# VA-Meter.net
KiCad netlist of a schematic drawn in EAGLE
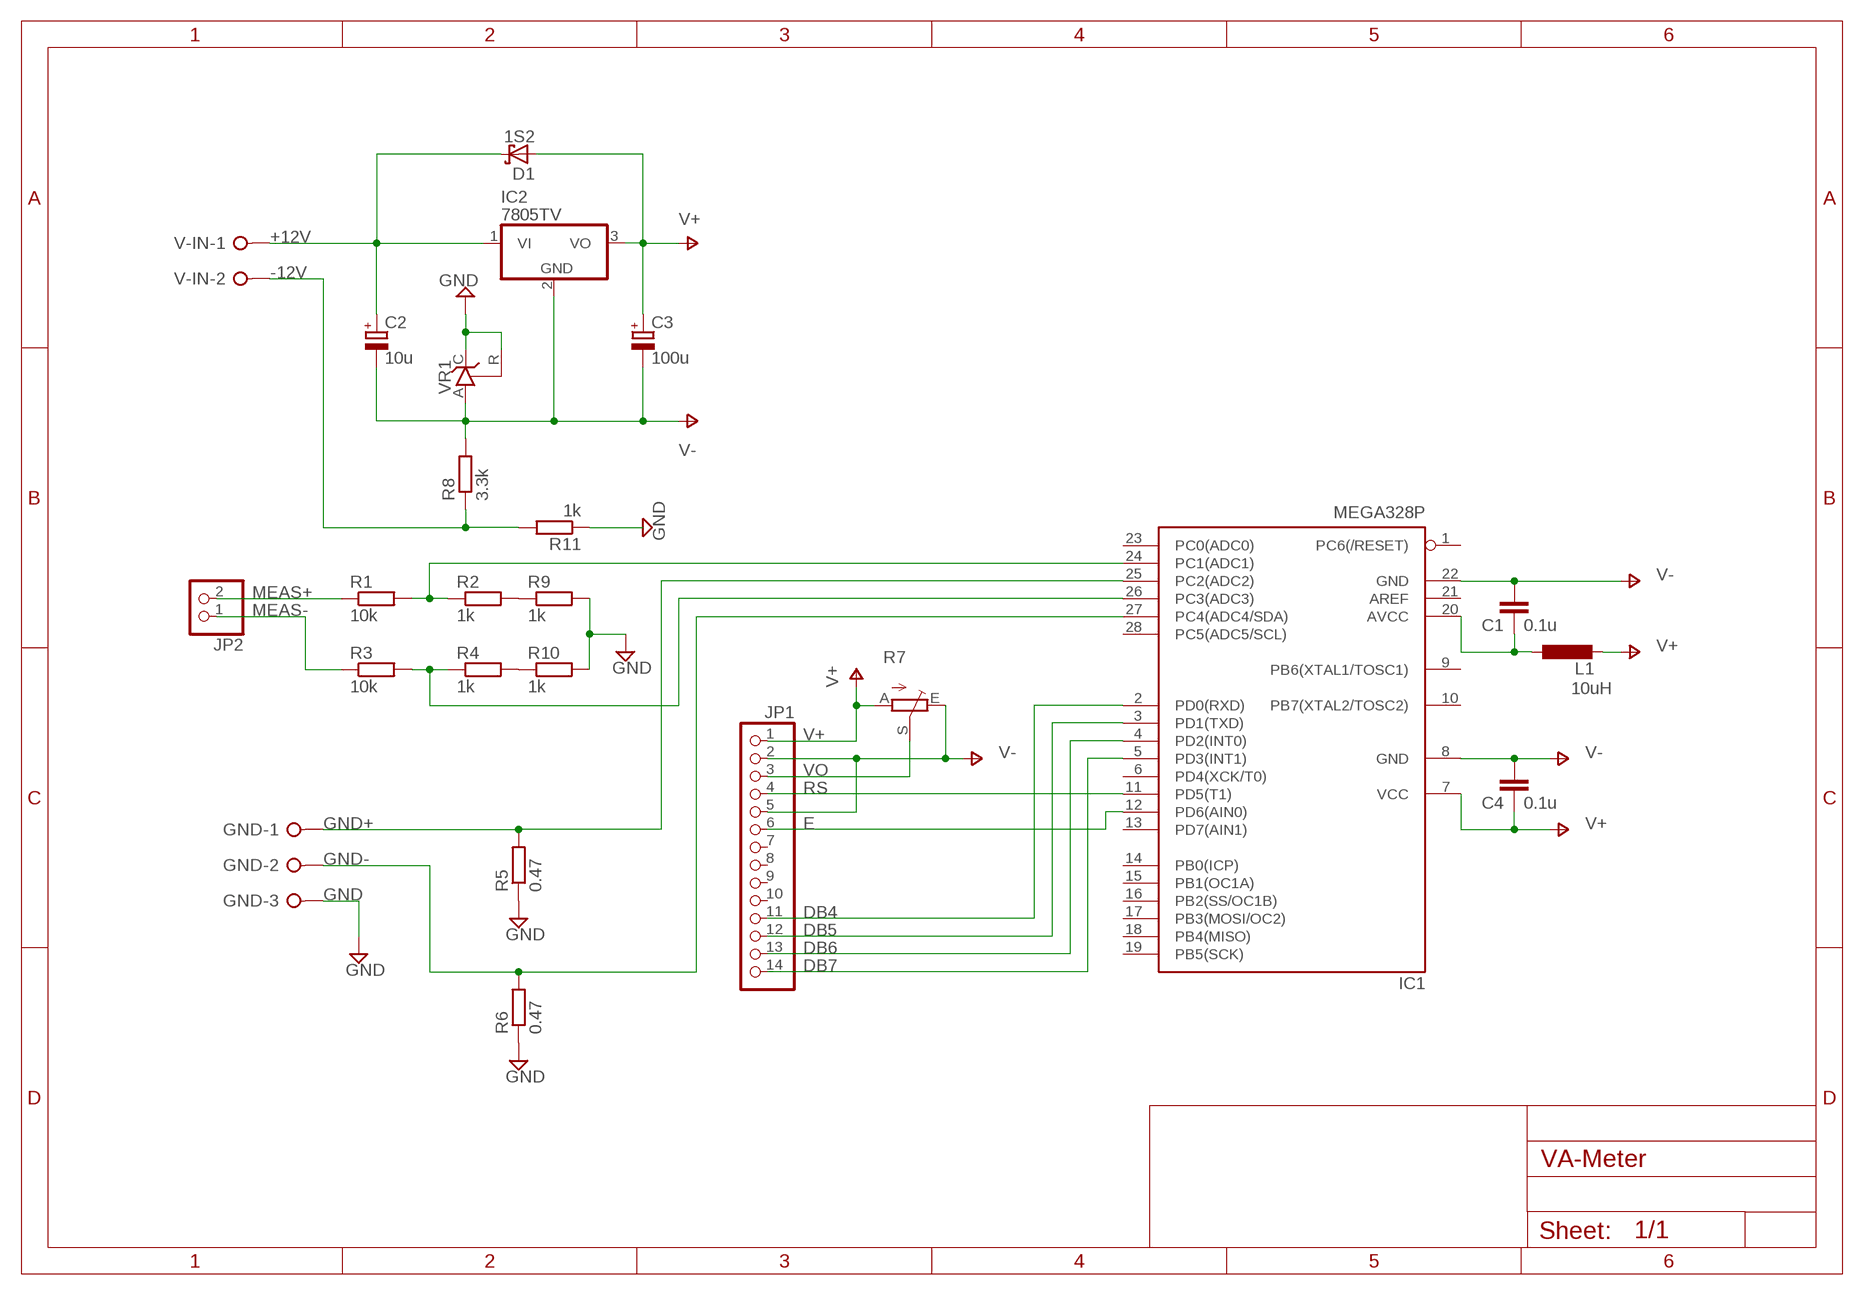
[diagram p0: schematic, sheet 1]

(export (version "E")
  (design (tool "Eeschema 10.0.6"))
  (components
    (comp (ref "C1")
      (value "0.1u")
      (footprint "eagle-import:C050-024X044")
      (libsource (lib "eagle-import") (part "C-EU050-024X044"))
    )
    (comp (ref "C2")
      (value "10u")
      (footprint "eagle-import:E2,5-5")
      (libsource (lib "eagle-import") (part "CPOL-EUE2.5-5"))
    )
    (comp (ref "C3")
      (value "100u")
      (footprint "eagle-import:E2,5-6")
      (libsource (lib "eagle-import") (part "CPOL-EUE2.5-6"))
    )
    (comp (ref "C4")
      (value "0.1u")
      (footprint "eagle-import:C050-024X044")
      (libsource (lib "eagle-import") (part "C-EU050-024X044"))
    )
    (comp (ref "D1")
      (value "1S2")
      (footprint "eagle-import:CB417-15")
      (libsource (lib "eagle-import") (part "SCHOTTKY-DIODECB417-15"))
    )
    (comp (ref "GND")
      (value "W237-03P")
      (footprint "eagle-import:W237-133")
      (libsource (lib "eagle-import") (part "W237-03P"))
    )
    (comp (ref "IC1")
      (value "MEGA328P")
      (footprint "eagle-import:MEGA328P")
      (libsource (lib "eagle-import") (part "MEGA328P"))
    )
    (comp (ref "IC2")
      (value "7805TV")
      (footprint "eagle-import:TO220V")
      (libsource (lib "eagle-import") (part "78TV05"))
    )
    (comp (ref "JP1")
      (value "PINHD-1X14")
      (footprint "eagle-import:1X14")
      (libsource (lib "eagle-import") (part "PINHD-1X14"))
    )
    (comp (ref "JP2")
      (value "PINHD-1X2")
      (footprint "eagle-import:1X02")
      (libsource (lib "eagle-import") (part "PINHD-1X2"))
    )
    (comp (ref "L1")
      (value "10uH")
      (footprint "eagle-import:6000-XXXX-RC")
      (libsource (lib "eagle-import") (part "L-EU6000-XXX-RC"))
    )
    (comp (ref "R1")
      (value "10k")
      (footprint "eagle-import:0207_7")
      (libsource (lib "eagle-import") (part "R-EU_0207/7"))
    )
    (comp (ref "R2")
      (value "1k")
      (footprint "eagle-import:0207_7")
      (libsource (lib "eagle-import") (part "R-EU_0207/7"))
    )
    (comp (ref "R3")
      (value "10k")
      (footprint "eagle-import:0207_7")
      (libsource (lib "eagle-import") (part "R-EU_0207/7"))
    )
    (comp (ref "R4")
      (value "1k")
      (footprint "eagle-import:0207_7")
      (libsource (lib "eagle-import") (part "R-EU_0207/7"))
    )
    (comp (ref "R5")
      (value "0.47")
      (footprint "eagle-import:P0613_15")
      (libsource (lib "eagle-import") (part "R-EU_0613/15"))
    )
    (comp (ref "R6")
      (value "0.47")
      (footprint "eagle-import:P0613_15")
      (libsource (lib "eagle-import") (part "R-EU_0613/15"))
    )
    (comp (ref "R7")
      (value "TRIM_EU-B25P")
      (footprint "eagle-import:B25P")
      (libsource (lib "eagle-import") (part "TRIM_EU-B25P"))
    )
    (comp (ref "R8")
      (value "3.3k")
      (footprint "eagle-import:P0613_15")
      (libsource (lib "eagle-import") (part "R-EU_0613/15"))
    )
    (comp (ref "R9")
      (value "1k")
      (footprint "eagle-import:0207_7")
      (libsource (lib "eagle-import") (part "R-EU_0207/7"))
    )
    (comp (ref "R10")
      (value "1k")
      (footprint "eagle-import:0207_7")
      (libsource (lib "eagle-import") (part "R-EU_0207/7"))
    )
    (comp (ref "R11")
      (value "1k")
      (footprint "eagle-import:P0613_15")
      (libsource (lib "eagle-import") (part "R-EU_0613/15"))
    )
    (comp (ref "V-IN")
      (value "W237-02P")
      (footprint "eagle-import:W237-132")
      (libsource (lib "eagle-import") (part "W237-02P"))
    )
    (comp (ref "VR1")
      (value "TL431CLP")
      (footprint "eagle-import:TO92-CLP")
      (libsource (lib "eagle-import") (part "TL431CLP"))
    )
  )
  (nets
    (net (code "1") (name "/+12V") (class "Default")
      (node (ref "C2") (pin "+") (pinfunction "+_+") (pintype "passive"))
      (node (ref "D1") (pin "C") (pinfunction "C_C") (pintype "passive"))
      (node (ref "IC2") (pin "1") (pinfunction "VI_1") (pintype "input"))
      (node (ref "V-IN") (pin "1") (pinfunction "KL_1") (pintype "passive"))
    )
    (net (code "2") (name "/-12V") (class "Default")
      (node (ref "R11") (pin "2") (pinfunction "2_2") (pintype "passive"))
      (node (ref "R8") (pin "1") (pinfunction "1_1") (pintype "passive"))
      (node (ref "V-IN") (pin "2") (pinfunction "KL_2") (pintype "passive"))
    )
    (net (code "3") (name "/DB4") (class "Default")
      (node (ref "IC1") (pin "2") (pinfunction "PD0(RXD)_2") (pintype "bidirectional"))
      (node (ref "JP1") (pin "11") (pinfunction "11_11") (pintype "passive"))
    )
    (net (code "4") (name "/DB5") (class "Default")
      (node (ref "IC1") (pin "3") (pinfunction "PD1(TXD)_3") (pintype "bidirectional"))
      (node (ref "JP1") (pin "12") (pinfunction "12_12") (pintype "passive"))
    )
    (net (code "5") (name "/DB6") (class "Default")
      (node (ref "IC1") (pin "4") (pinfunction "PD2(INT0)_4") (pintype "bidirectional"))
      (node (ref "JP1") (pin "13") (pinfunction "13_13") (pintype "passive"))
    )
    (net (code "6") (name "/DB7") (class "Default")
      (node (ref "IC1") (pin "5") (pinfunction "PD3(INT1)_5") (pintype "bidirectional"))
      (node (ref "JP1") (pin "14") (pinfunction "14_14") (pintype "passive"))
    )
    (net (code "7") (name "/E") (class "Default")
      (node (ref "IC1") (pin "12") (pinfunction "PD6(AIN0)_12") (pintype "bidirectional"))
      (node (ref "JP1") (pin "6") (pinfunction "6_6") (pintype "passive"))
    )
    (net (code "8") (name "/GND+") (class "Default")
      (node (ref "GND") (pin "1") (pinfunction "KL_1") (pintype "passive"))
      (node (ref "IC1") (pin "25") (pinfunction "PC2(ADC2)_25") (pintype "bidirectional"))
      (node (ref "R5") (pin "2") (pinfunction "2_2") (pintype "passive"))
    )
    (net (code "9") (name "/GND-") (class "Default")
      (node (ref "GND") (pin "2") (pinfunction "KL_2") (pintype "passive"))
      (node (ref "IC1") (pin "27") (pinfunction "PC4(ADC4/SDA)_27") (pintype "bidirectional"))
      (node (ref "R6") (pin "2") (pinfunction "2_2") (pintype "passive"))
    )
    (net (code "10") (name "/MEAS+") (class "Default")
      (node (ref "JP2") (pin "2") (pinfunction "2_2") (pintype "passive"))
      (node (ref "R1") (pin "1") (pinfunction "1_1") (pintype "passive"))
    )
    (net (code "11") (name "/MEAS-") (class "Default")
      (node (ref "JP2") (pin "1") (pinfunction "1_1") (pintype "passive"))
      (node (ref "R3") (pin "1") (pinfunction "1_1") (pintype "passive"))
    )
    (net (code "12") (name "/RS") (class "Default")
      (node (ref "IC1") (pin "11") (pinfunction "PD5(T1)_11") (pintype "bidirectional"))
      (node (ref "JP1") (pin "4") (pinfunction "4_4") (pintype "passive"))
    )
    (net (code "13") (name "/VO") (class "Default")
      (node (ref "JP1") (pin "3") (pinfunction "3_3") (pintype "passive"))
      (node (ref "R7") (pin "S") (pinfunction "S_S") (pintype "passive"))
    )
    (net (code "14") (name "GND") (class "Default")
      (node (ref "GND") (pin "3") (pinfunction "KL_3") (pintype "passive"))
      (node (ref "R10") (pin "2") (pinfunction "2_2") (pintype "passive"))
      (node (ref "R5") (pin "1") (pinfunction "1_1") (pintype "passive"))
      (node (ref "R6") (pin "1") (pinfunction "1_1") (pintype "passive"))
      (node (ref "R9") (pin "2") (pinfunction "2_2") (pintype "passive"))
      (node (ref "VR1") (pin "C") (pinfunction "C_C") (pintype "passive"))
      (node (ref "VR1") (pin "R") (pinfunction "R_R") (pintype "passive"))
    )
    (net (code "15") (name "Net-(IC1-AVCC)") (class "Default")
      (node (ref "C1") (pin "1") (pinfunction "1_1") (pintype "passive"))
      (node (ref "IC1") (pin "20") (pinfunction "AVCC_20") (pintype "power_in"))
      (node (ref "L1") (pin "1") (pinfunction "1_1") (pintype "passive"))
    )
    (net (code "16") (name "Net-(IC1-PC1(ADC1))") (class "Default")
      (node (ref "IC1") (pin "24") (pinfunction "PC1(ADC1)_24") (pintype "bidirectional"))
      (node (ref "R1") (pin "2") (pinfunction "2_2") (pintype "passive"))
      (node (ref "R2") (pin "1") (pinfunction "1_1") (pintype "passive"))
    )
    (net (code "17") (name "Net-(IC1-PC3(ADC3))") (class "Default")
      (node (ref "IC1") (pin "26") (pinfunction "PC3(ADC3)_26") (pintype "bidirectional"))
      (node (ref "R3") (pin "2") (pinfunction "2_2") (pintype "passive"))
      (node (ref "R4") (pin "1") (pinfunction "1_1") (pintype "passive"))
    )
    (net (code "18") (name "Net-(R2-Pad2)") (class "Default")
      (node (ref "R2") (pin "2") (pinfunction "2_2") (pintype "passive"))
      (node (ref "R9") (pin "1") (pinfunction "1_1") (pintype "passive"))
    )
    (net (code "19") (name "Net-(R10-Pad1)") (class "Default")
      (node (ref "R10") (pin "1") (pinfunction "1_1") (pintype "passive"))
      (node (ref "R4") (pin "2") (pinfunction "2_2") (pintype "passive"))
    )
    (net (code "20") (name "V+") (class "Default")
      (node (ref "C3") (pin "+") (pinfunction "+_+") (pintype "passive"))
      (node (ref "C4") (pin "1") (pinfunction "1_1") (pintype "passive"))
      (node (ref "D1") (pin "A") (pinfunction "A_A") (pintype "passive"))
      (node (ref "IC1") (pin "7") (pinfunction "VCC_7") (pintype "power_in"))
      (node (ref "IC2") (pin "3") (pinfunction "VO_3") (pintype "passive"))
      (node (ref "JP1") (pin "1") (pinfunction "1_1") (pintype "passive"))
      (node (ref "L1") (pin "2") (pinfunction "2_2") (pintype "passive"))
      (node (ref "R7") (pin "A") (pinfunction "A_A") (pintype "passive"))
    )
    (net (code "21") (name "V-") (class "Default")
      (node (ref "C1") (pin "2") (pinfunction "2_2") (pintype "passive"))
      (node (ref "C2") (pin "-") (pinfunction "-_-") (pintype "passive"))
      (node (ref "C3") (pin "-") (pinfunction "-_-") (pintype "passive"))
      (node (ref "C4") (pin "2") (pinfunction "2_2") (pintype "passive"))
      (node (ref "IC1") (pin "22") (pinfunction "GND_22") (pintype "power_in"))
      (node (ref "IC1") (pin "8") (pinfunction "GND_8") (pintype "power_in"))
      (node (ref "IC2") (pin "2") (pinfunction "GND_2") (pintype "passive"))
      (node (ref "JP1") (pin "2") (pinfunction "2_2") (pintype "passive"))
      (node (ref "JP1") (pin "5") (pinfunction "5_5") (pintype "passive"))
      (node (ref "R7") (pin "E") (pinfunction "E_E") (pintype "passive"))
      (node (ref "R8") (pin "2") (pinfunction "2_2") (pintype "passive"))
      (node (ref "VR1") (pin "A") (pinfunction "A_A") (pintype "passive"))
    )
    (net (code "22") (name "unconnected-(IC1-AREF-Pad21)") (class "Default")
      (node (ref "IC1") (pin "21") (pinfunction "AREF_21") (pintype "passive"))
    )
    (net (code "23") (name "unconnected-(IC1-PB0(ICP)-Pad14)") (class "Default")
      (node (ref "IC1") (pin "14") (pinfunction "PB0(ICP)_14") (pintype "bidirectional"))
    )
    (net (code "24") (name "unconnected-(IC1-PB1(OC1A)-Pad15)") (class "Default")
      (node (ref "IC1") (pin "15") (pinfunction "PB1(OC1A)_15") (pintype "bidirectional"))
    )
    (net (code "25") (name "unconnected-(IC1-PB2(SS{slash}OC1B)-Pad16)") (class "Default")
      (node (ref "IC1") (pin "16") (pinfunction "PB2(SS/OC1B)_16") (pintype "bidirectional"))
    )
    (net (code "26") (name "unconnected-(IC1-PB3(MOSI{slash}OC2)-Pad17)") (class "Default")
      (node (ref "IC1") (pin "17") (pinfunction "PB3(MOSI/OC2)_17") (pintype "bidirectional"))
    )
    (net (code "27") (name "unconnected-(IC1-PB4(MISO)-Pad18)") (class "Default")
      (node (ref "IC1") (pin "18") (pinfunction "PB4(MISO)_18") (pintype "bidirectional"))
    )
    (net (code "28") (name "unconnected-(IC1-PB5(SCK)-Pad19)") (class "Default")
      (node (ref "IC1") (pin "19") (pinfunction "PB5(SCK)_19") (pintype "bidirectional"))
    )
    (net (code "29") (name "unconnected-(IC1-PB6(XTAL1{slash}TOSC1)-Pad9)") (class "Default")
      (node (ref "IC1") (pin "9") (pinfunction "PB6(XTAL1/TOSC1)_9") (pintype "bidirectional"))
    )
    (net (code "30") (name "unconnected-(IC1-PB7(XTAL2{slash}TOSC2)-Pad10)") (class "Default")
      (node (ref "IC1") (pin "10") (pinfunction "PB7(XTAL2/TOSC2)_10") (pintype "bidirectional"))
    )
    (net (code "31") (name "unconnected-(IC1-PC0(ADC0)-Pad23)") (class "Default")
      (node (ref "IC1") (pin "23") (pinfunction "PC0(ADC0)_23") (pintype "bidirectional"))
    )
    (net (code "32") (name "unconnected-(IC1-PC5(ADC5{slash}SCL)-Pad28)") (class "Default")
      (node (ref "IC1") (pin "28") (pinfunction "PC5(ADC5/SCL)_28") (pintype "bidirectional"))
    )
    (net (code "33") (name "unconnected-(IC1-PC6({slash}RESET)-Pad1)") (class "Default")
      (node (ref "IC1") (pin "1") (pinfunction "PC6(/RESET)_1") (pintype "bidirectional"))
    )
    (net (code "34") (name "unconnected-(IC1-PD4(XCK{slash}T0)-Pad6)") (class "Default")
      (node (ref "IC1") (pin "6") (pinfunction "PD4(XCK/T0)_6") (pintype "bidirectional"))
    )
    (net (code "35") (name "unconnected-(IC1-PD7(AIN1)-Pad13)") (class "Default")
      (node (ref "IC1") (pin "13") (pinfunction "PD7(AIN1)_13") (pintype "bidirectional"))
    )
    (net (code "36") (name "unconnected-(JP1-Pad7)") (class "Default")
      (node (ref "JP1") (pin "7") (pinfunction "7_7") (pintype "passive"))
    )
    (net (code "37") (name "unconnected-(JP1-Pad8)") (class "Default")
      (node (ref "JP1") (pin "8") (pinfunction "8_8") (pintype "passive"))
    )
    (net (code "38") (name "unconnected-(JP1-Pad9)") (class "Default")
      (node (ref "JP1") (pin "9") (pinfunction "9_9") (pintype "passive"))
    )
    (net (code "39") (name "unconnected-(JP1-Pad10)") (class "Default")
      (node (ref "JP1") (pin "10") (pinfunction "10_10") (pintype "passive"))
    )
    (net (code "40") (name "unconnected-(R11-Pad1)") (class "Default")
      (node (ref "R11") (pin "1") (pinfunction "1_1") (pintype "passive"))
    )
  )
)
